# bq2550_shield.net
KiCad netlist of a schematic drawn in EAGLE
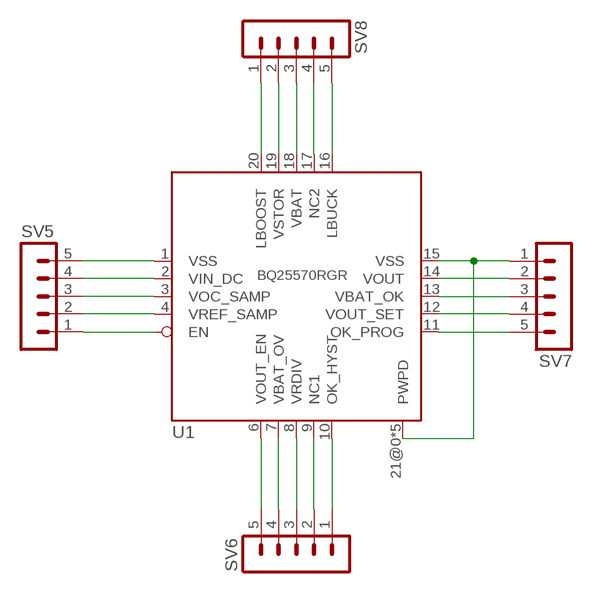
[diagram p0: schematic, sheet 1]

(export (version "E")
  (design (tool "Eeschema 10.0.6"))
  (components
    (comp (ref "SV5")
      (value "MA05-1")
      (footprint "eagle-import:MA05-1")
      (libsource (lib "eagle-import") (part "MA05-1"))
    )
    (comp (ref "SV6")
      (value "MA05-1")
      (footprint "eagle-import:MA05-1")
      (libsource (lib "eagle-import") (part "MA05-1"))
    )
    (comp (ref "SV7")
      (value "MA05-1")
      (footprint "eagle-import:MA05-1")
      (libsource (lib "eagle-import") (part "MA05-1"))
    )
    (comp (ref "SV8")
      (value "MA05-1")
      (footprint "eagle-import:MA05-1")
      (libsource (lib "eagle-import") (part "MA05-1"))
    )
    (comp (ref "U1")
      (value "BQ25570RGR")
      (footprint "eagle-import:QFN20")
      (libsource (lib "eagle-import") (part "BQ25570RGR"))
    )
  )
  (nets
    (net (code "1") (name "Net-(SV5-Pad5)") (class "Default")
      (node (ref "SV5") (pin "5") (pinfunction "5_5") (pintype "passive"))
      (node (ref "U1") (pin "1") (pinfunction "VSS_1") (pintype "power_in"))
    )
    (net (code "2") (name "Net-(SV7-Pad1)") (class "Default")
      (node (ref "SV7") (pin "1") (pinfunction "1_1") (pintype "passive"))
      (node (ref "U1") (pin "15") (pinfunction "VSS_15") (pintype "power_in"))
      (node (ref "U1") (pin "21@0") (pinfunction "PWPD_21@0") (pintype "power_in"))
      (node (ref "U1") (pin "21@1") (pinfunction "PWPD_21@1") (pintype "power_in"))
      (node (ref "U1") (pin "21@2") (pinfunction "PWPD_21@2") (pintype "power_in"))
      (node (ref "U1") (pin "21@3") (pinfunction "PWPD_21@3") (pintype "power_in"))
      (node (ref "U1") (pin "21@4") (pinfunction "PWPD_21@4") (pintype "power_in"))
    )
    (net (code "3") (name "Net-(U1-EN)") (class "Default")
      (node (ref "SV5") (pin "1") (pinfunction "1_1") (pintype "passive"))
      (node (ref "U1") (pin "5") (pinfunction "EN_5") (pintype "input"))
    )
    (net (code "4") (name "Net-(U1-LBOOST)") (class "Default")
      (node (ref "SV8") (pin "1") (pinfunction "1_1") (pintype "passive"))
      (node (ref "U1") (pin "20") (pinfunction "LBOOST_20") (pintype "power_in"))
    )
    (net (code "5") (name "Net-(U1-LBUCK)") (class "Default")
      (node (ref "SV8") (pin "5") (pinfunction "5_5") (pintype "passive"))
      (node (ref "U1") (pin "16") (pinfunction "LBUCK_16") (pintype "power_in"))
    )
    (net (code "6") (name "Net-(U1-NC1)") (class "Default")
      (node (ref "SV6") (pin "2") (pinfunction "2_2") (pintype "passive"))
      (node (ref "U1") (pin "9") (pinfunction "NC1_9") (pintype "power_in"))
    )
    (net (code "7") (name "Net-(U1-NC2)") (class "Default")
      (node (ref "SV8") (pin "4") (pinfunction "4_4") (pintype "passive"))
      (node (ref "U1") (pin "17") (pinfunction "NC2_17") (pintype "power_in"))
    )
    (net (code "8") (name "Net-(U1-OK_HYST)") (class "Default")
      (node (ref "SV6") (pin "1") (pinfunction "1_1") (pintype "passive"))
      (node (ref "U1") (pin "10") (pinfunction "OK_HYST_10") (pintype "input"))
    )
    (net (code "9") (name "Net-(U1-OK_PROG)") (class "Default")
      (node (ref "SV7") (pin "5") (pinfunction "5_5") (pintype "passive"))
      (node (ref "U1") (pin "11") (pinfunction "OK_PROG_11") (pintype "input"))
    )
    (net (code "10") (name "Net-(U1-VBAT)") (class "Default")
      (node (ref "SV8") (pin "3") (pinfunction "3_3") (pintype "passive"))
      (node (ref "U1") (pin "18") (pinfunction "VBAT_18") (pintype "power_in"))
    )
    (net (code "11") (name "Net-(U1-VBAT_OK)") (class "Default")
      (node (ref "SV7") (pin "3") (pinfunction "3_3") (pintype "passive"))
      (node (ref "U1") (pin "13") (pinfunction "VBAT_OK_13") (pintype "output"))
    )
    (net (code "12") (name "Net-(U1-VBAT_OV)") (class "Default")
      (node (ref "SV6") (pin "4") (pinfunction "4_4") (pintype "passive"))
      (node (ref "U1") (pin "7") (pinfunction "VBAT_OV_7") (pintype "input"))
    )
    (net (code "13") (name "Net-(U1-VIN_DC)") (class "Default")
      (node (ref "SV5") (pin "4") (pinfunction "4_4") (pintype "passive"))
      (node (ref "U1") (pin "2") (pinfunction "VIN_DC_2") (pintype "power_in"))
    )
    (net (code "14") (name "Net-(U1-VOC_SAMP)") (class "Default")
      (node (ref "SV5") (pin "3") (pinfunction "3_3") (pintype "passive"))
      (node (ref "U1") (pin "3") (pinfunction "VOC_SAMP_3") (pintype "input"))
    )
    (net (code "15") (name "Net-(U1-VOUT)") (class "Default")
      (node (ref "SV7") (pin "2") (pinfunction "2_2") (pintype "passive"))
      (node (ref "U1") (pin "14") (pinfunction "VOUT_14") (pintype "power_in"))
    )
    (net (code "16") (name "Net-(U1-VOUT_EN)") (class "Default")
      (node (ref "SV6") (pin "5") (pinfunction "5_5") (pintype "passive"))
      (node (ref "U1") (pin "6") (pinfunction "VOUT_EN_6") (pintype "input"))
    )
    (net (code "17") (name "Net-(U1-VOUT_SET)") (class "Default")
      (node (ref "SV7") (pin "4") (pinfunction "4_4") (pintype "passive"))
      (node (ref "U1") (pin "12") (pinfunction "VOUT_SET_12") (pintype "input"))
    )
    (net (code "18") (name "Net-(U1-VRDIV)") (class "Default")
      (node (ref "SV6") (pin "3") (pinfunction "3_3") (pintype "passive"))
      (node (ref "U1") (pin "8") (pinfunction "VRDIV_8") (pintype "bidirectional"))
    )
    (net (code "19") (name "Net-(U1-VREF_SAMP)") (class "Default")
      (node (ref "SV5") (pin "2") (pinfunction "2_2") (pintype "passive"))
      (node (ref "U1") (pin "4") (pinfunction "VREF_SAMP_4") (pintype "input"))
    )
    (net (code "20") (name "Net-(U1-VSTOR)") (class "Default")
      (node (ref "SV8") (pin "2") (pinfunction "2_2") (pintype "passive"))
      (node (ref "U1") (pin "19") (pinfunction "VSTOR_19") (pintype "bidirectional"))
    )
  )
)
